# BESt-module_v_1_3.net
KiCad netlist of a schematic drawn in EAGLE
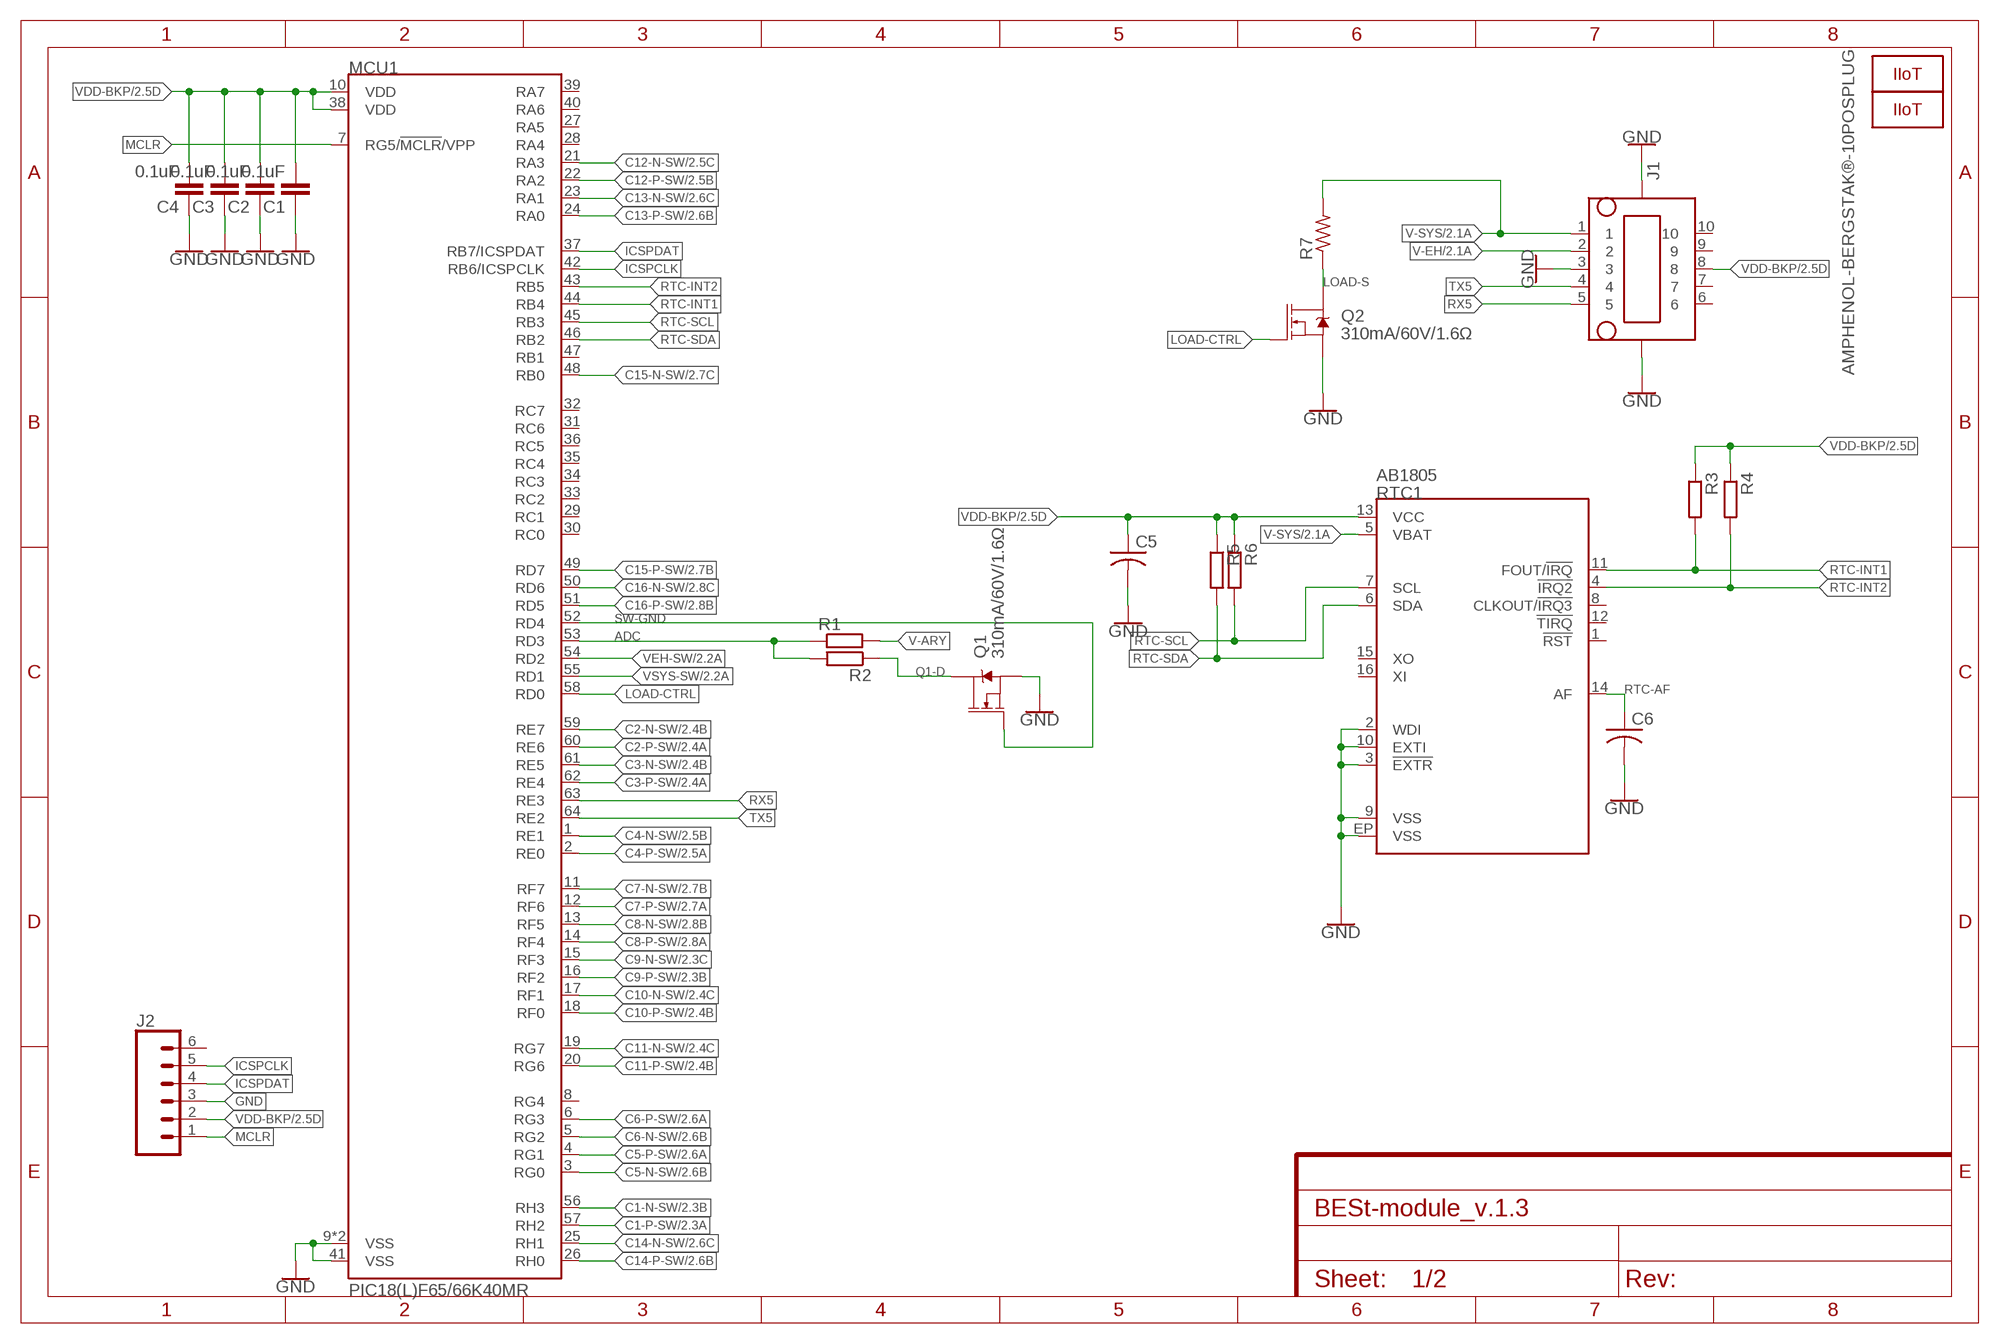
[diagram p0: schematic, sheet 1]
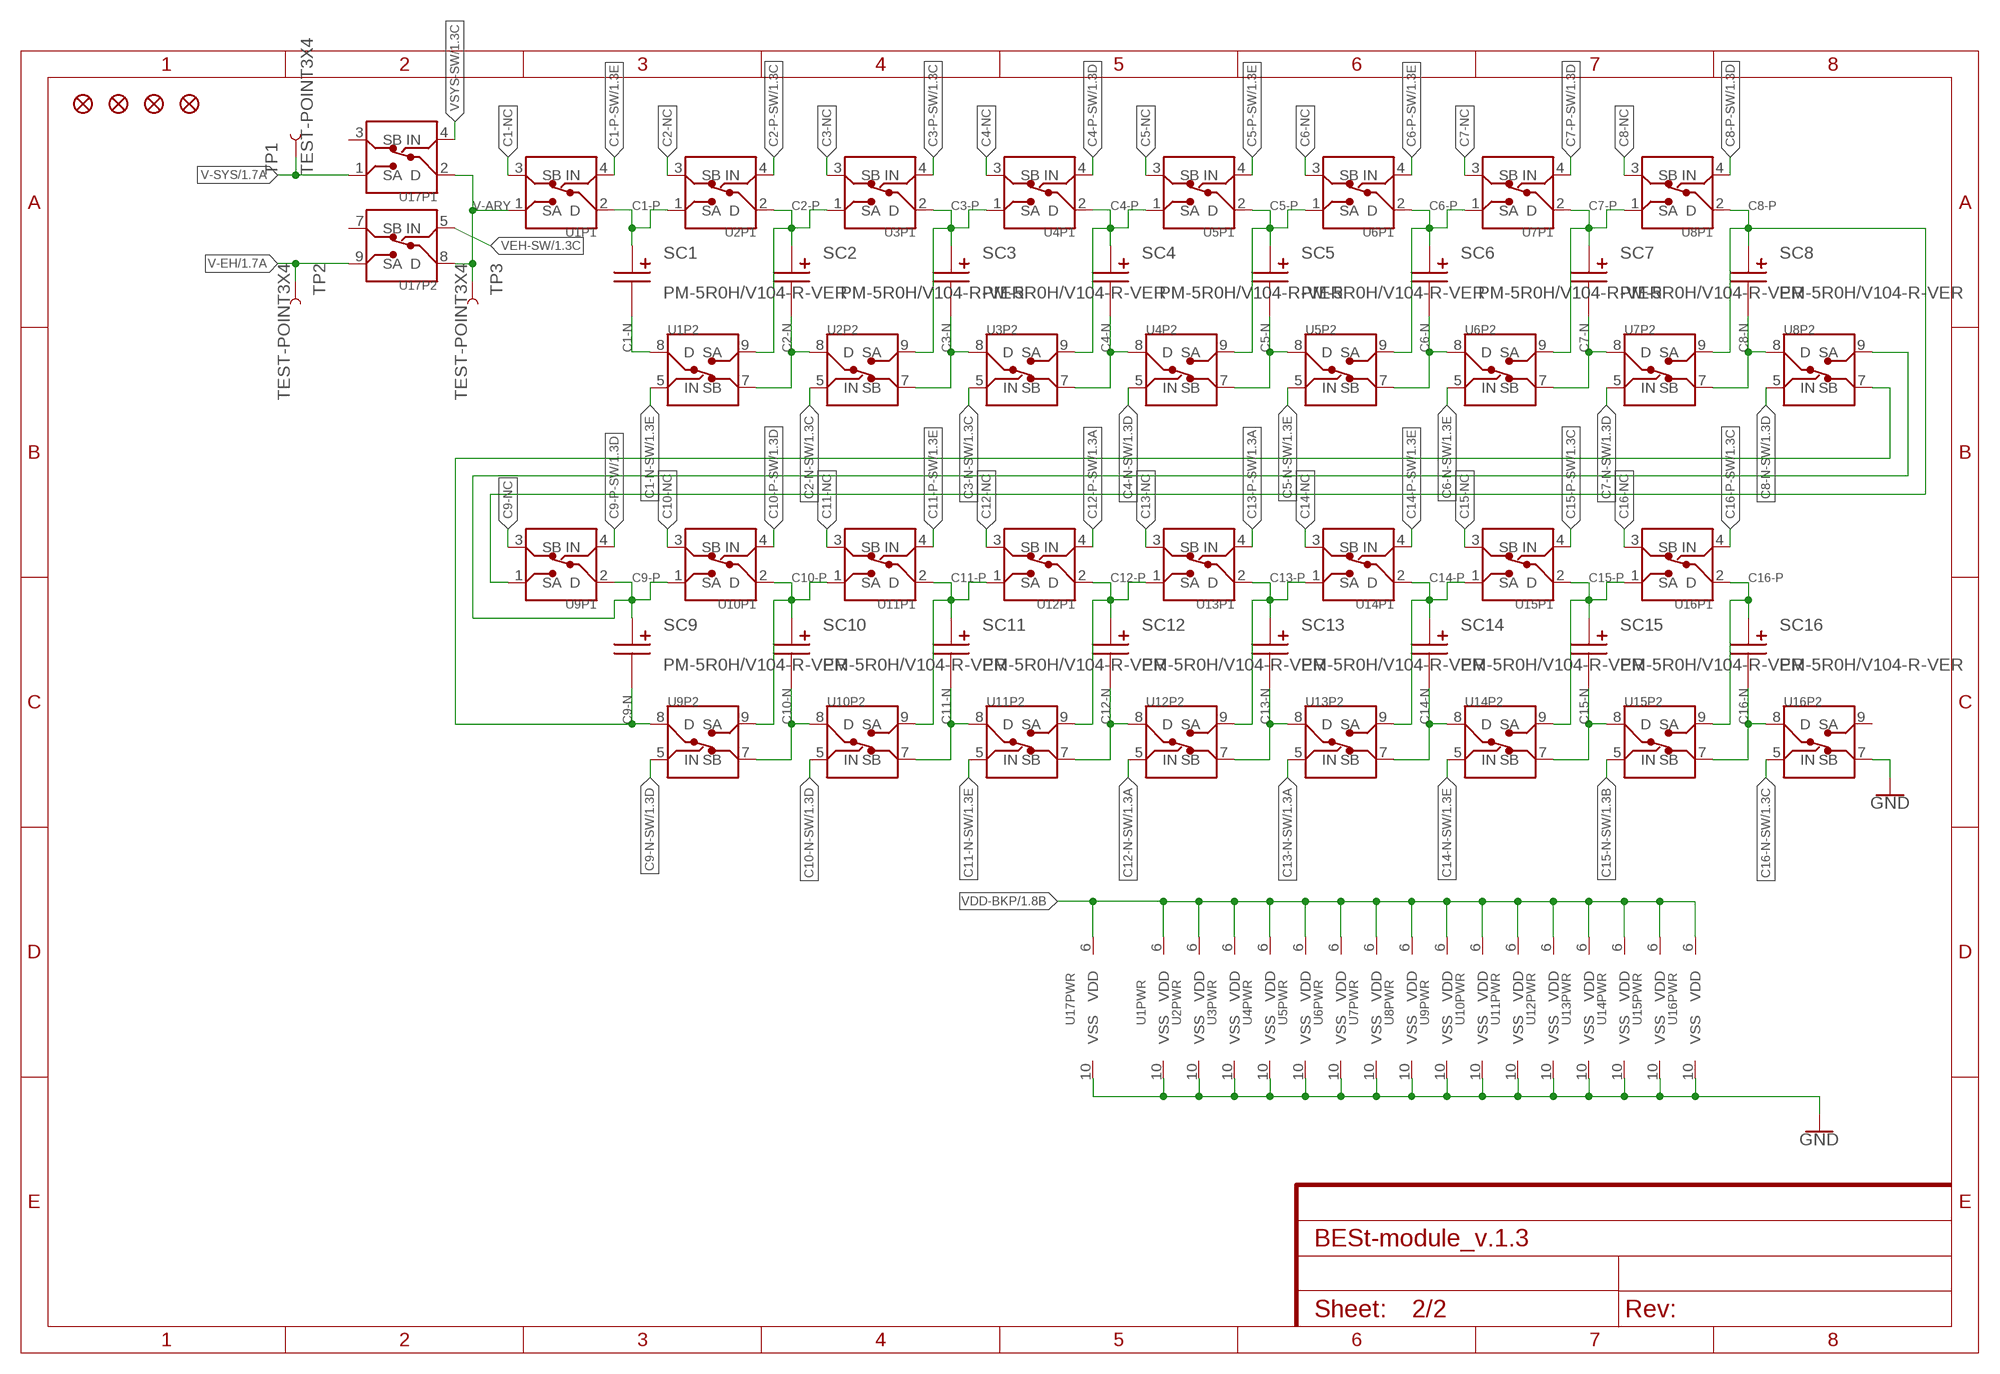
[diagram p1: schematic, sheet 2]

(export (version "E")
  (design (tool "Eeschema 10.0.6"))
  (components
    (comp (ref "FD1")
      (value "FIDUCIAL1X2")
      (footprint "eagle-import:FIDUCIAL-1X2")
      (libsource (lib "eagle-import") (part "FIDUCIAL1X2"))
    )
    (comp (ref "FD2")
      (value "FIDUCIAL1X2")
      (footprint "eagle-import:FIDUCIAL-1X2")
      (libsource (lib "eagle-import") (part "FIDUCIAL1X2"))
    )
    (comp (ref "FD3")
      (value "FIDUCIAL1X2")
      (footprint "eagle-import:FIDUCIAL-1X2")
      (libsource (lib "eagle-import") (part "FIDUCIAL1X2"))
    )
    (comp (ref "FD4")
      (value "FIDUCIAL1X2")
      (footprint "eagle-import:FIDUCIAL-1X2")
      (libsource (lib "eagle-import") (part "FIDUCIAL1X2"))
    )
    (comp (ref "SC1")
      (value "PM-5R0H/V104-R-VER")
      (footprint "eagle-import:EATON-13X11.3X6-V")
      (libsource (lib "eagle-import") (part "PM-5R0H/V104-R-VER"))
    )
    (comp (ref "SC2")
      (value "PM-5R0H/V104-R-VER")
      (footprint "eagle-import:EATON-13X11.3X6-V")
      (libsource (lib "eagle-import") (part "PM-5R0H/V104-R-VER"))
    )
    (comp (ref "SC3")
      (value "PM-5R0H/V104-R-VER")
      (footprint "eagle-import:EATON-13X11.3X6-V")
      (libsource (lib "eagle-import") (part "PM-5R0H/V104-R-VER"))
    )
    (comp (ref "SC4")
      (value "PM-5R0H/V104-R-VER")
      (footprint "eagle-import:EATON-13X11.3X6-V")
      (libsource (lib "eagle-import") (part "PM-5R0H/V104-R-VER"))
    )
    (comp (ref "SC5")
      (value "PM-5R0H/V104-R-VER")
      (footprint "eagle-import:EATON-13X11.3X6-V")
      (libsource (lib "eagle-import") (part "PM-5R0H/V104-R-VER"))
    )
    (comp (ref "SC6")
      (value "PM-5R0H/V104-R-VER")
      (footprint "eagle-import:EATON-13X11.3X6-V")
      (libsource (lib "eagle-import") (part "PM-5R0H/V104-R-VER"))
    )
    (comp (ref "SC7")
      (value "PM-5R0H/V104-R-VER")
      (footprint "eagle-import:EATON-13X11.3X6-V")
      (libsource (lib "eagle-import") (part "PM-5R0H/V104-R-VER"))
    )
    (comp (ref "SC8")
      (value "PM-5R0H/V104-R-VER")
      (footprint "eagle-import:EATON-13X11.3X6-V")
      (libsource (lib "eagle-import") (part "PM-5R0H/V104-R-VER"))
    )
    (comp (ref "SC9")
      (value "PM-5R0H/V104-R-VER")
      (footprint "eagle-import:EATON-13X11.3X6-V")
      (libsource (lib "eagle-import") (part "PM-5R0H/V104-R-VER"))
    )
    (comp (ref "SC10")
      (value "PM-5R0H/V104-R-VER")
      (footprint "eagle-import:EATON-13X11.3X6-V")
      (libsource (lib "eagle-import") (part "PM-5R0H/V104-R-VER"))
    )
    (comp (ref "SC11")
      (value "PM-5R0H/V104-R-VER")
      (footprint "eagle-import:EATON-13X11.3X6-V")
      (libsource (lib "eagle-import") (part "PM-5R0H/V104-R-VER"))
    )
    (comp (ref "SC12")
      (value "PM-5R0H/V104-R-VER")
      (footprint "eagle-import:EATON-13X11.3X6-V")
      (libsource (lib "eagle-import") (part "PM-5R0H/V104-R-VER"))
    )
    (comp (ref "SC13")
      (value "PM-5R0H/V104-R-VER")
      (footprint "eagle-import:EATON-13X11.3X6-V")
      (libsource (lib "eagle-import") (part "PM-5R0H/V104-R-VER"))
    )
    (comp (ref "SC14")
      (value "PM-5R0H/V104-R-VER")
      (footprint "eagle-import:EATON-13X11.3X6-V")
      (libsource (lib "eagle-import") (part "PM-5R0H/V104-R-VER"))
    )
    (comp (ref "SC15")
      (value "PM-5R0H/V104-R-VER")
      (footprint "eagle-import:EATON-13X11.3X6-V")
      (libsource (lib "eagle-import") (part "PM-5R0H/V104-R-VER"))
    )
    (comp (ref "SC16")
      (value "PM-5R0H/V104-R-VER")
      (footprint "eagle-import:EATON-13X11.3X6-V")
      (libsource (lib "eagle-import") (part "PM-5R0H/V104-R-VER"))
    )
    (comp (ref "TP1")
      (value "TEST-POINT3X4")
      (footprint "eagle-import:PAD.03X.04")
      (libsource (lib "eagle-import") (part "TEST-POINT3X4"))
    )
    (comp (ref "TP2")
      (value "TEST-POINT3X4")
      (footprint "eagle-import:PAD.03X.04")
      (libsource (lib "eagle-import") (part "TEST-POINT3X4"))
    )
    (comp (ref "TP3")
      (value "TEST-POINT3X4")
      (footprint "eagle-import:PAD.03X.04")
      (libsource (lib "eagle-import") (part "TEST-POINT3X4"))
    )
    (comp (ref "U1")
      (value "ADG824")
      (footprint "eagle-import:CP-10-10")
      (libsource (lib "eagle-import") (part "ADG824"))
    )
    (comp (ref "U2")
      (value "ADG824")
      (footprint "eagle-import:CP-10-10")
      (libsource (lib "eagle-import") (part "ADG824"))
    )
    (comp (ref "U3")
      (value "ADG824")
      (footprint "eagle-import:CP-10-10")
      (libsource (lib "eagle-import") (part "ADG824"))
    )
    (comp (ref "U4")
      (value "ADG824")
      (footprint "eagle-import:CP-10-10")
      (libsource (lib "eagle-import") (part "ADG824"))
    )
    (comp (ref "U5")
      (value "ADG824")
      (footprint "eagle-import:CP-10-10")
      (libsource (lib "eagle-import") (part "ADG824"))
    )
    (comp (ref "U6")
      (value "ADG824")
      (footprint "eagle-import:CP-10-10")
      (libsource (lib "eagle-import") (part "ADG824"))
    )
    (comp (ref "U7")
      (value "ADG824")
      (footprint "eagle-import:CP-10-10")
      (libsource (lib "eagle-import") (part "ADG824"))
    )
    (comp (ref "U8")
      (value "ADG824")
      (footprint "eagle-import:CP-10-10")
      (libsource (lib "eagle-import") (part "ADG824"))
    )
    (comp (ref "U9")
      (value "ADG824")
      (footprint "eagle-import:CP-10-10")
      (libsource (lib "eagle-import") (part "ADG824"))
    )
    (comp (ref "U10")
      (value "ADG824")
      (footprint "eagle-import:CP-10-10")
      (libsource (lib "eagle-import") (part "ADG824"))
    )
    (comp (ref "U11")
      (value "ADG824")
      (footprint "eagle-import:CP-10-10")
      (libsource (lib "eagle-import") (part "ADG824"))
    )
    (comp (ref "U12")
      (value "ADG824")
      (footprint "eagle-import:CP-10-10")
      (libsource (lib "eagle-import") (part "ADG824"))
    )
    (comp (ref "U13")
      (value "ADG824")
      (footprint "eagle-import:CP-10-10")
      (libsource (lib "eagle-import") (part "ADG824"))
    )
    (comp (ref "U14")
      (value "ADG824")
      (footprint "eagle-import:CP-10-10")
      (libsource (lib "eagle-import") (part "ADG824"))
    )
    (comp (ref "U15")
      (value "ADG824")
      (footprint "eagle-import:CP-10-10")
      (libsource (lib "eagle-import") (part "ADG824"))
    )
    (comp (ref "U16")
      (value "ADG824")
      (footprint "eagle-import:CP-10-10")
      (libsource (lib "eagle-import") (part "ADG824"))
    )
    (comp (ref "U17")
      (value "ADG824")
      (footprint "eagle-import:CP-10-10")
      (libsource (lib "eagle-import") (part "ADG824"))
    )
    (comp (ref "C1")
      (value "0.1uF")
      (footprint "eagle-import:0603")
      (libsource (lib "eagle-import") (part "0.1UF-0603-25V-5%"))
    )
    (comp (ref "C2")
      (value "0.1uF")
      (footprint "eagle-import:0603")
      (libsource (lib "eagle-import") (part "0.1UF-0603-25V-5%"))
    )
    (comp (ref "C3")
      (value "0.1uF")
      (footprint "eagle-import:0603")
      (libsource (lib "eagle-import") (part "0.1UF-0603-25V-5%"))
    )
    (comp (ref "C4")
      (value "0.1uF")
      (footprint "eagle-import:0603")
      (libsource (lib "eagle-import") (part "0.1UF-0603-25V-5%"))
    )
    (comp (ref "C5")
      (value "C-USC0402")
      (footprint "eagle-import:C0402")
      (libsource (lib "eagle-import") (part "C-USC0402"))
    )
    (comp (ref "C6")
      (value "C-USC0402")
      (footprint "eagle-import:C0402")
      (libsource (lib "eagle-import") (part "C-USC0402"))
    )
    (comp (ref "J1")
      (value "AMPHENOL-BERGSTAK®-10POSPLUG")
      (footprint "eagle-import:10132797-10POS-PLUG")
      (libsource (lib "eagle-import") (part "AMPHENOL-BERGSTAK®-10POSPLUG"))
    )
    (comp (ref "J2")
      (value "CONN_06NO_SILK_NO_POP")
      (footprint "eagle-import:1X06_NO_SILK")
      (libsource (lib "eagle-import") (part "CONN_06NO_SILK_NO_POP"))
    )
    (comp (ref "LOGO1")
      (value "IIOT")
      (footprint "eagle-import:IIOT")
      (libsource (lib "eagle-import") (part "IIOT"))
    )
    (comp (ref "LOGO2")
      (value "IIOT")
      (footprint "eagle-import:IIOT")
      (libsource (lib "eagle-import") (part "IIOT"))
    )
    (comp (ref "MCU1")
      (value "PIC18(L)F65/66K40MR")
      (footprint "eagle-import:QFN50P900X900X100-65T715N")
      (libsource (lib "eagle-import") (part "PIC18(L)F65/66K40MR"))
    )
    (comp (ref "Q1")
      (value "310mA/60V/1.6Ω")
      (footprint "eagle-import:SOT323")
      (libsource (lib "eagle-import") (part "MOSFET-NCH-2N7002PW"))
    )
    (comp (ref "Q2")
      (value "310mA/60V/1.6Ω")
      (footprint "eagle-import:SOT323")
      (libsource (lib "eagle-import") (part "MOSFET-NCH-2N7002PW"))
    )
    (comp (ref "R1")
      (value "R-EU_R0402")
      (footprint "eagle-import:R0402")
      (libsource (lib "eagle-import") (part "R-EU_R0402"))
    )
    (comp (ref "R2")
      (value "R-EU_R0402")
      (footprint "eagle-import:R0402")
      (libsource (lib "eagle-import") (part "R-EU_R0402"))
    )
    (comp (ref "R3")
      (value "R-EU_R0402")
      (footprint "eagle-import:R0402")
      (libsource (lib "eagle-import") (part "R-EU_R0402"))
    )
    (comp (ref "R4")
      (value "R-EU_R0402")
      (footprint "eagle-import:R0402")
      (libsource (lib "eagle-import") (part "R-EU_R0402"))
    )
    (comp (ref "R5")
      (value "R-EU_R0402")
      (footprint "eagle-import:R0402")
      (libsource (lib "eagle-import") (part "R-EU_R0402"))
    )
    (comp (ref "R6")
      (value "R-EU_R0402")
      (footprint "eagle-import:R0402")
      (libsource (lib "eagle-import") (part "R-EU_R0402"))
    )
    (comp (ref "R7")
      (value "R-US_R0805")
      (footprint "eagle-import:R0805")
      (libsource (lib "eagle-import") (part "R-US_R0805"))
    )
    (comp (ref "RTC1")
      (value "AB1805")
      (footprint "eagle-import:QFN-16-3X3")
      (libsource (lib "eagle-import") (part "AB1805"))
    )
  )
  (nets
    (net (code "1") (name "ADC") (class "Default")
      (node (ref "MCU1") (pin "53") (pinfunction "RD3_53") (pintype "bidirectional"))
      (node (ref "R1") (pin "1") (pinfunction "1_1") (pintype "passive"))
      (node (ref "R2") (pin "2") (pinfunction "2_2") (pintype "passive"))
    )
    (net (code "2") (name "C1-N") (class "Default")
      (node (ref "SC1") (pin "N") (pinfunction "N_N") (pintype "bidirectional"))
      (node (ref "U1") (pin "8") (pinfunction "D_8") (pintype "bidirectional"))
    )
    (net (code "3") (name "C1-N-SW") (class "Default")
      (node (ref "MCU1") (pin "56") (pinfunction "RH3_56") (pintype "bidirectional"))
      (node (ref "U1") (pin "5") (pinfunction "IN_5") (pintype "bidirectional"))
    )
    (net (code "4") (name "C1-NC") (class "Default")
      (node (ref "U1") (pin "3") (pinfunction "SB_3") (pintype "bidirectional"))
    )
    (net (code "5") (name "C1-P") (class "Default")
      (node (ref "SC1") (pin "P") (pinfunction "P_P") (pintype "bidirectional"))
      (node (ref "U1") (pin "2") (pinfunction "D_2") (pintype "bidirectional"))
      (node (ref "U2") (pin "1") (pinfunction "SA_1") (pintype "bidirectional"))
    )
    (net (code "6") (name "C1-P-SW") (class "Default")
      (node (ref "MCU1") (pin "57") (pinfunction "RH2_57") (pintype "bidirectional"))
      (node (ref "U1") (pin "4") (pinfunction "IN_4") (pintype "bidirectional"))
    )
    (net (code "7") (name "C2-N") (class "Default")
      (node (ref "SC2") (pin "N") (pinfunction "N_N") (pintype "bidirectional"))
      (node (ref "U1") (pin "7") (pinfunction "SB_7") (pintype "bidirectional"))
      (node (ref "U2") (pin "8") (pinfunction "D_8") (pintype "bidirectional"))
    )
    (net (code "8") (name "C2-N-SW") (class "Default")
      (node (ref "MCU1") (pin "59") (pinfunction "RE7_59") (pintype "bidirectional"))
      (node (ref "U2") (pin "5") (pinfunction "IN_5") (pintype "bidirectional"))
    )
    (net (code "9") (name "C2-NC") (class "Default")
      (node (ref "U2") (pin "3") (pinfunction "SB_3") (pintype "bidirectional"))
    )
    (net (code "10") (name "C2-P") (class "Default")
      (node (ref "SC2") (pin "P") (pinfunction "P_P") (pintype "bidirectional"))
      (node (ref "U1") (pin "9") (pinfunction "SA_9") (pintype "bidirectional"))
      (node (ref "U2") (pin "2") (pinfunction "D_2") (pintype "bidirectional"))
      (node (ref "U3") (pin "1") (pinfunction "SA_1") (pintype "bidirectional"))
    )
    (net (code "11") (name "C2-P-SW") (class "Default")
      (node (ref "MCU1") (pin "60") (pinfunction "RE6_60") (pintype "bidirectional"))
      (node (ref "U2") (pin "4") (pinfunction "IN_4") (pintype "bidirectional"))
    )
    (net (code "12") (name "C3-N") (class "Default")
      (node (ref "SC3") (pin "N") (pinfunction "N_N") (pintype "bidirectional"))
      (node (ref "U2") (pin "7") (pinfunction "SB_7") (pintype "bidirectional"))
      (node (ref "U3") (pin "8") (pinfunction "D_8") (pintype "bidirectional"))
    )
    (net (code "13") (name "C3-N-SW") (class "Default")
      (node (ref "MCU1") (pin "61") (pinfunction "RE5_61") (pintype "bidirectional"))
      (node (ref "U3") (pin "5") (pinfunction "IN_5") (pintype "bidirectional"))
    )
    (net (code "14") (name "C3-NC") (class "Default")
      (node (ref "U3") (pin "3") (pinfunction "SB_3") (pintype "bidirectional"))
    )
    (net (code "15") (name "C3-P") (class "Default")
      (node (ref "SC3") (pin "P") (pinfunction "P_P") (pintype "bidirectional"))
      (node (ref "U2") (pin "9") (pinfunction "SA_9") (pintype "bidirectional"))
      (node (ref "U3") (pin "2") (pinfunction "D_2") (pintype "bidirectional"))
      (node (ref "U4") (pin "1") (pinfunction "SA_1") (pintype "bidirectional"))
    )
    (net (code "16") (name "C3-P-SW") (class "Default")
      (node (ref "MCU1") (pin "62") (pinfunction "RE4_62") (pintype "bidirectional"))
      (node (ref "U3") (pin "4") (pinfunction "IN_4") (pintype "bidirectional"))
    )
    (net (code "17") (name "C4-N") (class "Default")
      (node (ref "SC4") (pin "N") (pinfunction "N_N") (pintype "bidirectional"))
      (node (ref "U3") (pin "7") (pinfunction "SB_7") (pintype "bidirectional"))
      (node (ref "U4") (pin "8") (pinfunction "D_8") (pintype "bidirectional"))
    )
    (net (code "18") (name "C4-N-SW") (class "Default")
      (node (ref "MCU1") (pin "1") (pinfunction "RE1_1") (pintype "bidirectional"))
      (node (ref "U4") (pin "5") (pinfunction "IN_5") (pintype "bidirectional"))
    )
    (net (code "19") (name "C4-NC") (class "Default")
      (node (ref "U4") (pin "3") (pinfunction "SB_3") (pintype "bidirectional"))
    )
    (net (code "20") (name "C4-P") (class "Default")
      (node (ref "SC4") (pin "P") (pinfunction "P_P") (pintype "bidirectional"))
      (node (ref "U3") (pin "9") (pinfunction "SA_9") (pintype "bidirectional"))
      (node (ref "U4") (pin "2") (pinfunction "D_2") (pintype "bidirectional"))
      (node (ref "U5") (pin "1") (pinfunction "SA_1") (pintype "bidirectional"))
    )
    (net (code "21") (name "C4-P-SW") (class "Default")
      (node (ref "MCU1") (pin "2") (pinfunction "RE0_2") (pintype "bidirectional"))
      (node (ref "U4") (pin "4") (pinfunction "IN_4") (pintype "bidirectional"))
    )
    (net (code "22") (name "C5-N") (class "Default")
      (node (ref "SC5") (pin "N") (pinfunction "N_N") (pintype "bidirectional"))
      (node (ref "U4") (pin "7") (pinfunction "SB_7") (pintype "bidirectional"))
      (node (ref "U5") (pin "8") (pinfunction "D_8") (pintype "bidirectional"))
    )
    (net (code "23") (name "C5-N-SW") (class "Default")
      (node (ref "MCU1") (pin "3") (pinfunction "RG0_3") (pintype "bidirectional"))
      (node (ref "U5") (pin "5") (pinfunction "IN_5") (pintype "bidirectional"))
    )
    (net (code "24") (name "C5-NC") (class "Default")
      (node (ref "U5") (pin "3") (pinfunction "SB_3") (pintype "bidirectional"))
    )
    (net (code "25") (name "C5-P") (class "Default")
      (node (ref "SC5") (pin "P") (pinfunction "P_P") (pintype "bidirectional"))
      (node (ref "U4") (pin "9") (pinfunction "SA_9") (pintype "bidirectional"))
      (node (ref "U5") (pin "2") (pinfunction "D_2") (pintype "bidirectional"))
      (node (ref "U6") (pin "1") (pinfunction "SA_1") (pintype "bidirectional"))
    )
    (net (code "26") (name "C5-P-SW") (class "Default")
      (node (ref "MCU1") (pin "4") (pinfunction "RG1_4") (pintype "bidirectional"))
      (node (ref "U5") (pin "4") (pinfunction "IN_4") (pintype "bidirectional"))
    )
    (net (code "27") (name "C6-N") (class "Default")
      (node (ref "SC6") (pin "N") (pinfunction "N_N") (pintype "bidirectional"))
      (node (ref "U5") (pin "7") (pinfunction "SB_7") (pintype "bidirectional"))
      (node (ref "U6") (pin "8") (pinfunction "D_8") (pintype "bidirectional"))
    )
    (net (code "28") (name "C6-N-SW") (class "Default")
      (node (ref "MCU1") (pin "5") (pinfunction "RG2_5") (pintype "bidirectional"))
      (node (ref "U6") (pin "5") (pinfunction "IN_5") (pintype "bidirectional"))
    )
    (net (code "29") (name "C6-NC") (class "Default")
      (node (ref "U6") (pin "3") (pinfunction "SB_3") (pintype "bidirectional"))
    )
    (net (code "30") (name "C6-P") (class "Default")
      (node (ref "SC6") (pin "P") (pinfunction "P_P") (pintype "bidirectional"))
      (node (ref "U5") (pin "9") (pinfunction "SA_9") (pintype "bidirectional"))
      (node (ref "U6") (pin "2") (pinfunction "D_2") (pintype "bidirectional"))
      (node (ref "U7") (pin "1") (pinfunction "SA_1") (pintype "bidirectional"))
    )
    (net (code "31") (name "C6-P-SW") (class "Default")
      (node (ref "MCU1") (pin "6") (pinfunction "RG3_6") (pintype "bidirectional"))
      (node (ref "U6") (pin "4") (pinfunction "IN_4") (pintype "bidirectional"))
    )
    (net (code "32") (name "C7-N") (class "Default")
      (node (ref "SC7") (pin "N") (pinfunction "N_N") (pintype "bidirectional"))
      (node (ref "U6") (pin "7") (pinfunction "SB_7") (pintype "bidirectional"))
      (node (ref "U7") (pin "8") (pinfunction "D_8") (pintype "bidirectional"))
    )
    (net (code "33") (name "C7-N-SW") (class "Default")
      (node (ref "MCU1") (pin "11") (pinfunction "RF7_11") (pintype "bidirectional"))
      (node (ref "U7") (pin "5") (pinfunction "IN_5") (pintype "bidirectional"))
    )
    (net (code "34") (name "C7-NC") (class "Default")
      (node (ref "U7") (pin "3") (pinfunction "SB_3") (pintype "bidirectional"))
    )
    (net (code "35") (name "C7-P") (class "Default")
      (node (ref "SC7") (pin "P") (pinfunction "P_P") (pintype "bidirectional"))
      (node (ref "U6") (pin "9") (pinfunction "SA_9") (pintype "bidirectional"))
      (node (ref "U7") (pin "2") (pinfunction "D_2") (pintype "bidirectional"))
      (node (ref "U8") (pin "1") (pinfunction "SA_1") (pintype "bidirectional"))
    )
    (net (code "36") (name "C7-P-SW") (class "Default")
      (node (ref "MCU1") (pin "12") (pinfunction "RF6_12") (pintype "bidirectional"))
      (node (ref "U7") (pin "4") (pinfunction "IN_4") (pintype "bidirectional"))
    )
    (net (code "37") (name "C8-N") (class "Default")
      (node (ref "SC8") (pin "N") (pinfunction "N_N") (pintype "bidirectional"))
      (node (ref "U7") (pin "7") (pinfunction "SB_7") (pintype "bidirectional"))
      (node (ref "U8") (pin "8") (pinfunction "D_8") (pintype "bidirectional"))
    )
    (net (code "38") (name "C8-N-SW") (class "Default")
      (node (ref "MCU1") (pin "13") (pinfunction "RF5_13") (pintype "bidirectional"))
      (node (ref "U8") (pin "5") (pinfunction "IN_5") (pintype "bidirectional"))
    )
    (net (code "39") (name "C8-NC") (class "Default")
      (node (ref "U8") (pin "3") (pinfunction "SB_3") (pintype "bidirectional"))
    )
    (net (code "40") (name "C8-P") (class "Default")
      (node (ref "SC8") (pin "P") (pinfunction "P_P") (pintype "bidirectional"))
      (node (ref "U7") (pin "9") (pinfunction "SA_9") (pintype "bidirectional"))
      (node (ref "U8") (pin "2") (pinfunction "D_2") (pintype "bidirectional"))
      (node (ref "U9") (pin "1") (pinfunction "SA_1") (pintype "bidirectional"))
    )
    (net (code "41") (name "C8-P-SW") (class "Default")
      (node (ref "MCU1") (pin "14") (pinfunction "RF4_14") (pintype "bidirectional"))
      (node (ref "U8") (pin "4") (pinfunction "IN_4") (pintype "bidirectional"))
    )
    (net (code "42") (name "C9-N") (class "Default")
      (node (ref "SC9") (pin "N") (pinfunction "N_N") (pintype "bidirectional"))
      (node (ref "U8") (pin "7") (pinfunction "SB_7") (pintype "bidirectional"))
      (node (ref "U9") (pin "8") (pinfunction "D_8") (pintype "bidirectional"))
    )
    (net (code "43") (name "C9-N-SW") (class "Default")
      (node (ref "MCU1") (pin "15") (pinfunction "RF3_15") (pintype "bidirectional"))
      (node (ref "U9") (pin "5") (pinfunction "IN_5") (pintype "bidirectional"))
    )
    (net (code "44") (name "C9-NC") (class "Default")
      (node (ref "U9") (pin "3") (pinfunction "SB_3") (pintype "bidirectional"))
    )
    (net (code "45") (name "C9-P") (class "Default")
      (node (ref "SC9") (pin "P") (pinfunction "P_P") (pintype "bidirectional"))
      (node (ref "U10") (pin "1") (pinfunction "SA_1") (pintype "bidirectional"))
      (node (ref "U8") (pin "9") (pinfunction "SA_9") (pintype "bidirectional"))
      (node (ref "U9") (pin "2") (pinfunction "D_2") (pintype "bidirectional"))
    )
    (net (code "46") (name "C9-P-SW") (class "Default")
      (node (ref "MCU1") (pin "16") (pinfunction "RF2_16") (pintype "bidirectional"))
      (node (ref "U9") (pin "4") (pinfunction "IN_4") (pintype "bidirectional"))
    )
    (net (code "47") (name "C10-N") (class "Default")
      (node (ref "SC10") (pin "N") (pinfunction "N_N") (pintype "bidirectional"))
      (node (ref "U10") (pin "8") (pinfunction "D_8") (pintype "bidirectional"))
      (node (ref "U9") (pin "7") (pinfunction "SB_7") (pintype "bidirectional"))
    )
    (net (code "48") (name "C10-N-SW") (class "Default")
      (node (ref "MCU1") (pin "17") (pinfunction "RF1_17") (pintype "bidirectional"))
      (node (ref "U10") (pin "5") (pinfunction "IN_5") (pintype "bidirectional"))
    )
    (net (code "49") (name "C10-NC") (class "Default")
      (node (ref "U10") (pin "3") (pinfunction "SB_3") (pintype "bidirectional"))
    )
    (net (code "50") (name "C10-P") (class "Default")
      (node (ref "SC10") (pin "P") (pinfunction "P_P") (pintype "bidirectional"))
      (node (ref "U10") (pin "2") (pinfunction "D_2") (pintype "bidirectional"))
      (node (ref "U11") (pin "1") (pinfunction "SA_1") (pintype "bidirectional"))
      (node (ref "U9") (pin "9") (pinfunction "SA_9") (pintype "bidirectional"))
    )
    (net (code "51") (name "C10-P-SW") (class "Default")
      (node (ref "MCU1") (pin "18") (pinfunction "RF0_18") (pintype "bidirectional"))
      (node (ref "U10") (pin "4") (pinfunction "IN_4") (pintype "bidirectional"))
    )
    (net (code "52") (name "C11-N") (class "Default")
      (node (ref "SC11") (pin "N") (pinfunction "N_N") (pintype "bidirectional"))
      (node (ref "U10") (pin "7") (pinfunction "SB_7") (pintype "bidirectional"))
      (node (ref "U11") (pin "8") (pinfunction "D_8") (pintype "bidirectional"))
    )
    (net (code "53") (name "C11-N-SW") (class "Default")
      (node (ref "MCU1") (pin "19") (pinfunction "RG7_19") (pintype "bidirectional"))
      (node (ref "U11") (pin "5") (pinfunction "IN_5") (pintype "bidirectional"))
    )
    (net (code "54") (name "C11-NC") (class "Default")
      (node (ref "U11") (pin "3") (pinfunction "SB_3") (pintype "bidirectional"))
    )
    (net (code "55") (name "C11-P") (class "Default")
      (node (ref "SC11") (pin "P") (pinfunction "P_P") (pintype "bidirectional"))
      (node (ref "U10") (pin "9") (pinfunction "SA_9") (pintype "bidirectional"))
      (node (ref "U11") (pin "2") (pinfunction "D_2") (pintype "bidirectional"))
      (node (ref "U12") (pin "1") (pinfunction "SA_1") (pintype "bidirectional"))
    )
    (net (code "56") (name "C11-P-SW") (class "Default")
      (node (ref "MCU1") (pin "20") (pinfunction "RG6_20") (pintype "bidirectional"))
      (node (ref "U11") (pin "4") (pinfunction "IN_4") (pintype "bidirectional"))
    )
    (net (code "57") (name "C12-N") (class "Default")
      (node (ref "SC12") (pin "N") (pinfunction "N_N") (pintype "bidirectional"))
      (node (ref "U11") (pin "7") (pinfunction "SB_7") (pintype "bidirectional"))
      (node (ref "U12") (pin "8") (pinfunction "D_8") (pintype "bidirectional"))
    )
    (net (code "58") (name "C12-N-SW") (class "Default")
      (node (ref "MCU1") (pin "21") (pinfunction "RA3_21") (pintype "bidirectional"))
      (node (ref "U12") (pin "5") (pinfunction "IN_5") (pintype "bidirectional"))
    )
    (net (code "59") (name "C12-NC") (class "Default")
      (node (ref "U12") (pin "3") (pinfunction "SB_3") (pintype "bidirectional"))
    )
    (net (code "60") (name "C12-P") (class "Default")
      (node (ref "SC12") (pin "P") (pinfunction "P_P") (pintype "bidirectional"))
      (node (ref "U11") (pin "9") (pinfunction "SA_9") (pintype "bidirectional"))
      (node (ref "U12") (pin "2") (pinfunction "D_2") (pintype "bidirectional"))
      (node (ref "U13") (pin "1") (pinfunction "SA_1") (pintype "bidirectional"))
    )
    (net (code "61") (name "C12-P-SW") (class "Default")
      (node (ref "MCU1") (pin "22") (pinfunction "RA2_22") (pintype "bidirectional"))
      (node (ref "U12") (pin "4") (pinfunction "IN_4") (pintype "bidirectional"))
    )
    (net (code "62") (name "C13-N") (class "Default")
      (node (ref "SC13") (pin "N") (pinfunction "N_N") (pintype "bidirectional"))
      (node (ref "U12") (pin "7") (pinfunction "SB_7") (pintype "bidirectional"))
      (node (ref "U13") (pin "8") (pinfunction "D_8") (pintype "bidirectional"))
    )
    (net (code "63") (name "C13-N-SW") (class "Default")
      (node (ref "MCU1") (pin "23") (pinfunction "RA1_23") (pintype "bidirectional"))
      (node (ref "U13") (pin "5") (pinfunction "IN_5") (pintype "bidirectional"))
    )
    (net (code "64") (name "C13-NC") (class "Default")
      (node (ref "U13") (pin "3") (pinfunction "SB_3") (pintype "bidirectional"))
    )
    (net (code "65") (name "C13-P") (class "Default")
      (node (ref "SC13") (pin "P") (pinfunction "P_P") (pintype "bidirectional"))
      (node (ref "U12") (pin "9") (pinfunction "SA_9") (pintype "bidirectional"))
      (node (ref "U13") (pin "2") (pinfunction "D_2") (pintype "bidirectional"))
      (node (ref "U14") (pin "1") (pinfunction "SA_1") (pintype "bidirectional"))
    )
    (net (code "66") (name "C13-P-SW") (class "Default")
      (node (ref "MCU1") (pin "24") (pinfunction "RA0_24") (pintype "bidirectional"))
      (node (ref "U13") (pin "4") (pinfunction "IN_4") (pintype "bidirectional"))
    )
    (net (code "67") (name "C14-N") (class "Default")
      (node (ref "SC14") (pin "N") (pinfunction "N_N") (pintype "bidirectional"))
      (node (ref "U13") (pin "7") (pinfunction "SB_7") (pintype "bidirectional"))
      (node (ref "U14") (pin "8") (pinfunction "D_8") (pintype "bidirectional"))
    )
    (net (code "68") (name "C14-N-SW") (class "Default")
      (node (ref "MCU1") (pin "25") (pinfunction "RH1_25") (pintype "bidirectional"))
      (node (ref "U14") (pin "5") (pinfunction "IN_5") (pintype "bidirectional"))
    )
    (net (code "69") (name "C14-NC") (class "Default")
      (node (ref "U14") (pin "3") (pinfunction "SB_3") (pintype "bidirectional"))
    )
    (net (code "70") (name "C14-P") (class "Default")
      (node (ref "SC14") (pin "P") (pinfunction "P_P") (pintype "bidirectional"))
      (node (ref "U13") (pin "9") (pinfunction "SA_9") (pintype "bidirectional"))
      (node (ref "U14") (pin "2") (pinfunction "D_2") (pintype "bidirectional"))
      (node (ref "U15") (pin "1") (pinfunction "SA_1") (pintype "bidirectional"))
    )
    (net (code "71") (name "C14-P-SW") (class "Default")
      (node (ref "MCU1") (pin "26") (pinfunction "RH0_26") (pintype "bidirectional"))
      (node (ref "U14") (pin "4") (pinfunction "IN_4") (pintype "bidirectional"))
    )
    (net (code "72") (name "C15-N") (class "Default")
      (node (ref "SC15") (pin "N") (pinfunction "N_N") (pintype "bidirectional"))
      (node (ref "U14") (pin "7") (pinfunction "SB_7") (pintype "bidirectional"))
      (node (ref "U15") (pin "8") (pinfunction "D_8") (pintype "bidirectional"))
    )
    (net (code "73") (name "C15-N-SW") (class "Default")
      (node (ref "MCU1") (pin "48") (pinfunction "RB0_48") (pintype "bidirectional"))
      (node (ref "U15") (pin "5") (pinfunction "IN_5") (pintype "bidirectional"))
    )
    (net (code "74") (name "C15-NC") (class "Default")
      (node (ref "U15") (pin "3") (pinfunction "SB_3") (pintype "bidirectional"))
    )
    (net (code "75") (name "C15-P") (class "Default")
      (node (ref "SC15") (pin "P") (pinfunction "P_P") (pintype "bidirectional"))
      (node (ref "U14") (pin "9") (pinfunction "SA_9") (pintype "bidirectional"))
      (node (ref "U15") (pin "2") (pinfunction "D_2") (pintype "bidirectional"))
      (node (ref "U16") (pin "1") (pinfunction "SA_1") (pintype "bidirectional"))
    )
    (net (code "76") (name "C15-P-SW") (class "Default")
      (node (ref "MCU1") (pin "49") (pinfunction "RD7_49") (pintype "bidirectional"))
      (node (ref "U15") (pin "4") (pinfunction "IN_4") (pintype "bidirectional"))
    )
    (net (code "77") (name "C16-N") (class "Default")
      (node (ref "SC16") (pin "N") (pinfunction "N_N") (pintype "bidirectional"))
      (node (ref "U15") (pin "7") (pinfunction "SB_7") (pintype "bidirectional"))
      (node (ref "U16") (pin "8") (pinfunction "D_8") (pintype "bidirectional"))
    )
    (net (code "78") (name "C16-N-SW") (class "Default")
      (node (ref "MCU1") (pin "50") (pinfunction "RD6_50") (pintype "bidirectional"))
      (node (ref "U16") (pin "5") (pinfunction "IN_5") (pintype "bidirectional"))
    )
    (net (code "79") (name "C16-NC") (class "Default")
      (node (ref "U16") (pin "3") (pinfunction "SB_3") (pintype "bidirectional"))
    )
    (net (code "80") (name "C16-P") (class "Default")
      (node (ref "SC16") (pin "P") (pinfunction "P_P") (pintype "bidirectional"))
      (node (ref "U15") (pin "9") (pinfunction "SA_9") (pintype "bidirectional"))
      (node (ref "U16") (pin "2") (pinfunction "D_2") (pintype "bidirectional"))
    )
    (net (code "81") (name "C16-P-SW") (class "Default")
      (node (ref "MCU1") (pin "51") (pinfunction "RD5_51") (pintype "bidirectional"))
      (node (ref "U16") (pin "4") (pinfunction "IN_4") (pintype "bidirectional"))
    )
    (net (code "82") (name "GND") (class "Default")
      (node (ref "C1") (pin "1") (pinfunction "1_1") (pintype "passive"))
      (node (ref "C2") (pin "1") (pinfunction "1_1") (pintype "passive"))
      (node (ref "C3") (pin "1") (pinfunction "1_1") (pintype "passive"))
      (node (ref "C4") (pin "1") (pinfunction "1_1") (pintype "passive"))
      (node (ref "C5") (pin "2") (pinfunction "2_2") (pintype "passive"))
      (node (ref "C6") (pin "2") (pinfunction "2_2") (pintype "passive"))
      (node (ref "J1") (pin "3") (pinfunction "3_3") (pintype "bidirectional"))
      (node (ref "J1") (pin "MNT1") (pinfunction "MNT1_MNT1") (pintype "bidirectional"))
      (node (ref "J1") (pin "MNT2") (pinfunction "MNT2_MNT2") (pintype "bidirectional"))
      (node (ref "J2") (pin "3") (pinfunction "3_3") (pintype "passive"))
      (node (ref "MCU1") (pin "41") (pinfunction "VSS_41") (pintype "bidirectional"))
      (node (ref "MCU1") (pin "65") (pinfunction "VSS_65") (pintype "bidirectional"))
      (node (ref "MCU1") (pin "9") (pinfunction "VSS_9") (pintype "bidirectional"))
      (node (ref "Q1") (pin "2") (pinfunction "S_2") (pintype "bidirectional"))
      (node (ref "Q2") (pin "2") (pinfunction "S_2") (pintype "bidirectional"))
      (node (ref "RTC1") (pin "10") (pinfunction "EXTI_10") (pintype "bidirectional"))
      (node (ref "RTC1") (pin "2") (pinfunction "WDI_2") (pintype "bidirectional"))
      (node (ref "RTC1") (pin "3") (pinfunction "~{EXTR}_3") (pintype "bidirectional"))
      (node (ref "RTC1") (pin "9") (pinfunction "VSS_9") (pintype "bidirectional"))
      (node (ref "RTC1") (pin "EP") (pinfunction "VSS_EP") (pintype "bidirectional"))
      (node (ref "U1") (pin "10") (pinfunction "VSS_10") (pintype "bidirectional"))
      (node (ref "U10") (pin "10") (pinfunction "VSS_10") (pintype "bidirectional"))
      (node (ref "U11") (pin "10") (pinfunction "VSS_10") (pintype "bidirectional"))
      (node (ref "U12") (pin "10") (pinfunction "VSS_10") (pintype "bidirectional"))
      (node (ref "U13") (pin "10") (pinfunction "VSS_10") (pintype "bidirectional"))
      (node (ref "U14") (pin "10") (pinfunction "VSS_10") (pintype "bidirectional"))
      (node (ref "U15") (pin "10") (pinfunction "VSS_10") (pintype "bidirectional"))
      (node (ref "U16") (pin "10") (pinfunction "VSS_10") (pintype "bidirectional"))
      (node (ref "U16") (pin "7") (pinfunction "SB_7") (pintype "bidirectional"))
      (node (ref "U17") (pin "10") (pinfunction "VSS_10") (pintype "bidirectional"))
      (node (ref "U2") (pin "10") (pinfunction "VSS_10") (pintype "bidirectional"))
      (node (ref "U3") (pin "10") (pinfunction "VSS_10") (pintype "bidirectional"))
      (node (ref "U4") (pin "10") (pinfunction "VSS_10") (pintype "bidirectional"))
      (node (ref "U5") (pin "10") (pinfunction "VSS_10") (pintype "bidirectional"))
      (node (ref "U6") (pin "10") (pinfunction "VSS_10") (pintype "bidirectional"))
      (node (ref "U7") (pin "10") (pinfunction "VSS_10") (pintype "bidirectional"))
      (node (ref "U8") (pin "10") (pinfunction "VSS_10") (pintype "bidirectional"))
      (node (ref "U9") (pin "10") (pinfunction "VSS_10") (pintype "bidirectional"))
    )
    (net (code "83") (name "ICSPCLK") (class "Default")
      (node (ref "J2") (pin "5") (pinfunction "5_5") (pintype "passive"))
      (node (ref "MCU1") (pin "42") (pinfunction "RB6/ICSPCLK_42") (pintype "bidirectional"))
    )
    (net (code "84") (name "ICSPDAT") (class "Default")
      (node (ref "J2") (pin "4") (pinfunction "4_4") (pintype "passive"))
      (node (ref "MCU1") (pin "37") (pinfunction "RB7/ICSPDAT_37") (pintype "bidirectional"))
    )
    (net (code "85") (name "LOAD-CTRL") (class "Default")
      (node (ref "MCU1") (pin "58") (pinfunction "RD0_58") (pintype "bidirectional"))
      (node (ref "Q2") (pin "1") (pinfunction "G_1") (pintype "bidirectional"))
    )
    (net (code "86") (name "LOAD-S") (class "Default")
      (node (ref "Q2") (pin "3") (pinfunction "D_3") (pintype "bidirectional"))
      (node (ref "R7") (pin "1") (pinfunction "1_1") (pintype "passive"))
    )
    (net (code "87") (name "MCLR") (class "Default")
      (node (ref "J2") (pin "1") (pinfunction "1_1") (pintype "passive"))
      (node (ref "MCU1") (pin "7") (pinfunction "RG5/~{MCLR}/VPP_7") (pintype "bidirectional"))
    )
    (net (code "88") (name "Q1-D") (class "Default")
      (node (ref "Q1") (pin "3") (pinfunction "D_3") (pintype "bidirectional"))
      (node (ref "R2") (pin "1") (pinfunction "1_1") (pintype "passive"))
    )
    (net (code "89") (name "RTC-AF") (class "Default")
      (node (ref "C6") (pin "1") (pinfunction "1_1") (pintype "passive"))
      (node (ref "RTC1") (pin "14") (pinfunction "AF_14") (pintype "bidirectional"))
    )
    (net (code "90") (name "RTC-INT1") (class "Default")
      (node (ref "MCU1") (pin "44") (pinfunction "RB4_44") (pintype "bidirectional"))
      (node (ref "R3") (pin "2") (pinfunction "2_2") (pintype "passive"))
      (node (ref "RTC1") (pin "11") (pinfunction "FOUT/~{IRQ}_11") (pintype "bidirectional"))
    )
    (net (code "91") (name "RTC-INT2") (class "Default")
      (node (ref "MCU1") (pin "43") (pinfunction "RB5_43") (pintype "bidirectional"))
      (node (ref "R4") (pin "2") (pinfunction "2_2") (pintype "passive"))
      (node (ref "RTC1") (pin "4") (pinfunction "~{IRQ2}_4") (pintype "bidirectional"))
    )
    (net (code "92") (name "RTC-SCL") (class "Default")
      (node (ref "MCU1") (pin "45") (pinfunction "RB3_45") (pintype "bidirectional"))
      (node (ref "R6") (pin "2") (pinfunction "2_2") (pintype "passive"))
      (node (ref "RTC1") (pin "7") (pinfunction "SCL_7") (pintype "bidirectional"))
    )
    (net (code "93") (name "RTC-SDA") (class "Default")
      (node (ref "MCU1") (pin "46") (pinfunction "RB2_46") (pintype "bidirectional"))
      (node (ref "R5") (pin "2") (pinfunction "2_2") (pintype "passive"))
      (node (ref "RTC1") (pin "6") (pinfunction "SDA_6") (pintype "bidirectional"))
    )
    (net (code "94") (name "RX5") (class "Default")
      (node (ref "J1") (pin "5") (pinfunction "5_5") (pintype "bidirectional"))
      (node (ref "MCU1") (pin "63") (pinfunction "RE3_63") (pintype "bidirectional"))
    )
    (net (code "95") (name "SW-GND") (class "Default")
      (node (ref "MCU1") (pin "52") (pinfunction "RD4_52") (pintype "bidirectional"))
      (node (ref "Q1") (pin "1") (pinfunction "G_1") (pintype "bidirectional"))
    )
    (net (code "96") (name "TX5") (class "Default")
      (node (ref "J1") (pin "4") (pinfunction "4_4") (pintype "bidirectional"))
      (node (ref "MCU1") (pin "64") (pinfunction "RE2_64") (pintype "bidirectional"))
    )
    (net (code "97") (name "V-ARY") (class "Default")
      (node (ref "R1") (pin "2") (pinfunction "2_2") (pintype "passive"))
      (node (ref "TP3") (pin "P$1") (pinfunction "1_P$1") (pintype "bidirectional"))
      (node (ref "U1") (pin "1") (pinfunction "SA_1") (pintype "bidirectional"))
      (node (ref "U17") (pin "2") (pinfunction "D_2") (pintype "bidirectional"))
      (node (ref "U17") (pin "8") (pinfunction "D_8") (pintype "bidirectional"))
    )
    (net (code "98") (name "V-EH") (class "Default")
      (node (ref "J1") (pin "2") (pinfunction "2_2") (pintype "bidirectional"))
      (node (ref "TP2") (pin "P$1") (pinfunction "1_P$1") (pintype "bidirectional"))
      (node (ref "U17") (pin "9") (pinfunction "SA_9") (pintype "bidirectional"))
    )
    (net (code "99") (name "V-SYS") (class "Default")
      (node (ref "J1") (pin "1") (pinfunction "1_1") (pintype "bidirectional"))
      (node (ref "R7") (pin "2") (pinfunction "2_2") (pintype "passive"))
      (node (ref "RTC1") (pin "5") (pinfunction "VBAT_5") (pintype "bidirectional"))
      (node (ref "TP1") (pin "P$1") (pinfunction "1_P$1") (pintype "bidirectional"))
      (node (ref "U17") (pin "1") (pinfunction "SA_1") (pintype "bidirectional"))
    )
    (net (code "100") (name "VDD-BKP") (class "Default")
      (node (ref "C1") (pin "2") (pinfunction "2_2") (pintype "passive"))
      (node (ref "C2") (pin "2") (pinfunction "2_2") (pintype "passive"))
      (node (ref "C3") (pin "2") (pinfunction "2_2") (pintype "passive"))
      (node (ref "C4") (pin "2") (pinfunction "2_2") (pintype "passive"))
      (node (ref "C5") (pin "1") (pinfunction "1_1") (pintype "passive"))
      (node (ref "J1") (pin "8") (pinfunction "8_8") (pintype "bidirectional"))
      (node (ref "J2") (pin "2") (pinfunction "2_2") (pintype "passive"))
      (node (ref "MCU1") (pin "10") (pinfunction "VDD_10") (pintype "bidirectional"))
      (node (ref "MCU1") (pin "38") (pinfunction "VDD_38") (pintype "bidirectional"))
      (node (ref "R3") (pin "1") (pinfunction "1_1") (pintype "passive"))
      (node (ref "R4") (pin "1") (pinfunction "1_1") (pintype "passive"))
      (node (ref "R5") (pin "1") (pinfunction "1_1") (pintype "passive"))
      (node (ref "R6") (pin "1") (pinfunction "1_1") (pintype "passive"))
      (node (ref "RTC1") (pin "13") (pinfunction "VCC_13") (pintype "bidirectional"))
      (node (ref "U1") (pin "6") (pinfunction "VDD_6") (pintype "bidirectional"))
      (node (ref "U10") (pin "6") (pinfunction "VDD_6") (pintype "bidirectional"))
      (node (ref "U11") (pin "6") (pinfunction "VDD_6") (pintype "bidirectional"))
      (node (ref "U12") (pin "6") (pinfunction "VDD_6") (pintype "bidirectional"))
      (node (ref "U13") (pin "6") (pinfunction "VDD_6") (pintype "bidirectional"))
      (node (ref "U14") (pin "6") (pinfunction "VDD_6") (pintype "bidirectional"))
      (node (ref "U15") (pin "6") (pinfunction "VDD_6") (pintype "bidirectional"))
      (node (ref "U16") (pin "6") (pinfunction "VDD_6") (pintype "bidirectional"))
      (node (ref "U17") (pin "6") (pinfunction "VDD_6") (pintype "bidirectional"))
      (node (ref "U2") (pin "6") (pinfunction "VDD_6") (pintype "bidirectional"))
      (node (ref "U3") (pin "6") (pinfunction "VDD_6") (pintype "bidirectional"))
      (node (ref "U4") (pin "6") (pinfunction "VDD_6") (pintype "bidirectional"))
      (node (ref "U5") (pin "6") (pinfunction "VDD_6") (pintype "bidirectional"))
      (node (ref "U6") (pin "6") (pinfunction "VDD_6") (pintype "bidirectional"))
      (node (ref "U7") (pin "6") (pinfunction "VDD_6") (pintype "bidirectional"))
      (node (ref "U8") (pin "6") (pinfunction "VDD_6") (pintype "bidirectional"))
      (node (ref "U9") (pin "6") (pinfunction "VDD_6") (pintype "bidirectional"))
    )
    (net (code "101") (name "VEH-SW") (class "Default")
      (node (ref "MCU1") (pin "54") (pinfunction "RD2_54") (pintype "bidirectional"))
      (node (ref "U17") (pin "5") (pinfunction "IN_5") (pintype "bidirectional"))
    )
    (net (code "102") (name "VSYS-SW") (class "Default")
      (node (ref "MCU1") (pin "55") (pinfunction "RD1_55") (pintype "bidirectional"))
      (node (ref "U17") (pin "4") (pinfunction "IN_4") (pintype "bidirectional"))
    )
    (net (code "103") (name "unconnected-(J1-Pad6)") (class "Default")
      (node (ref "J1") (pin "6") (pinfunction "6_6") (pintype "bidirectional"))
    )
    (net (code "104") (name "unconnected-(J1-Pad7)") (class "Default")
      (node (ref "J1") (pin "7") (pinfunction "7_7") (pintype "bidirectional"))
    )
    (net (code "105") (name "unconnected-(J1-Pad9)") (class "Default")
      (node (ref "J1") (pin "9") (pinfunction "9_9") (pintype "bidirectional"))
    )
    (net (code "106") (name "unconnected-(J1-Pad10)") (class "Default")
      (node (ref "J1") (pin "10") (pinfunction "10_10") (pintype "bidirectional"))
    )
    (net (code "107") (name "unconnected-(J2-Pad6)") (class "Default")
      (node (ref "J2") (pin "6") (pinfunction "6_6") (pintype "passive"))
    )
    (net (code "108") (name "unconnected-(MCU1-RA4-Pad28)") (class "Default")
      (node (ref "MCU1") (pin "28") (pinfunction "RA4_28") (pintype "bidirectional"))
    )
    (net (code "109") (name "unconnected-(MCU1-RA5-Pad27)") (class "Default")
      (node (ref "MCU1") (pin "27") (pinfunction "RA5_27") (pintype "bidirectional"))
    )
    (net (code "110") (name "unconnected-(MCU1-RA6-Pad40)") (class "Default")
      (node (ref "MCU1") (pin "40") (pinfunction "RA6_40") (pintype "bidirectional"))
    )
    (net (code "111") (name "unconnected-(MCU1-RA7-Pad39)") (class "Default")
      (node (ref "MCU1") (pin "39") (pinfunction "RA7_39") (pintype "bidirectional"))
    )
    (net (code "112") (name "unconnected-(MCU1-RB1-Pad47)") (class "Default")
      (node (ref "MCU1") (pin "47") (pinfunction "RB1_47") (pintype "bidirectional"))
    )
    (net (code "113") (name "unconnected-(MCU1-RC0-Pad30)") (class "Default")
      (node (ref "MCU1") (pin "30") (pinfunction "RC0_30") (pintype "bidirectional"))
    )
    (net (code "114") (name "unconnected-(MCU1-RC1-Pad29)") (class "Default")
      (node (ref "MCU1") (pin "29") (pinfunction "RC1_29") (pintype "bidirectional"))
    )
    (net (code "115") (name "unconnected-(MCU1-RC2-Pad33)") (class "Default")
      (node (ref "MCU1") (pin "33") (pinfunction "RC2_33") (pintype "bidirectional"))
    )
    (net (code "116") (name "unconnected-(MCU1-RC3-Pad34)") (class "Default")
      (node (ref "MCU1") (pin "34") (pinfunction "RC3_34") (pintype "bidirectional"))
    )
    (net (code "117") (name "unconnected-(MCU1-RC4-Pad35)") (class "Default")
      (node (ref "MCU1") (pin "35") (pinfunction "RC4_35") (pintype "bidirectional"))
    )
    (net (code "118") (name "unconnected-(MCU1-RC5-Pad36)") (class "Default")
      (node (ref "MCU1") (pin "36") (pinfunction "RC5_36") (pintype "bidirectional"))
    )
    (net (code "119") (name "unconnected-(MCU1-RC6-Pad31)") (class "Default")
      (node (ref "MCU1") (pin "31") (pinfunction "RC6_31") (pintype "bidirectional"))
    )
    (net (code "120") (name "unconnected-(MCU1-RC7-Pad32)") (class "Default")
      (node (ref "MCU1") (pin "32") (pinfunction "RC7_32") (pintype "bidirectional"))
    )
    (net (code "121") (name "unconnected-(MCU1-RG4-Pad8)") (class "Default")
      (node (ref "MCU1") (pin "8") (pinfunction "RG4_8") (pintype "bidirectional"))
    )
    (net (code "122") (name "unconnected-(RTC1-CLKOUT{slash}~{IRQ3}-Pad8)") (class "Default")
      (node (ref "RTC1") (pin "8") (pinfunction "CLKOUT/~{IRQ3}_8") (pintype "bidirectional"))
    )
    (net (code "123") (name "unconnected-(RTC1-XI-Pad16)") (class "Default")
      (node (ref "RTC1") (pin "16") (pinfunction "XI_16") (pintype "bidirectional"))
    )
    (net (code "124") (name "unconnected-(RTC1-XO-Pad15)") (class "Default")
      (node (ref "RTC1") (pin "15") (pinfunction "XO_15") (pintype "bidirectional"))
    )
    (net (code "125") (name "unconnected-(RTC1-~{RST}-Pad1)") (class "Default")
      (node (ref "RTC1") (pin "1") (pinfunction "~{RST}_1") (pintype "bidirectional"))
    )
    (net (code "126") (name "unconnected-(RTC1-~{TIRQ}-Pad12)") (class "Default")
      (node (ref "RTC1") (pin "12") (pinfunction "~{TIRQ}_12") (pintype "bidirectional"))
    )
    (net (code "127") (name "unconnected-(U16B-SA-Pad9)") (class "Default")
      (node (ref "U16") (pin "9") (pinfunction "SA_9") (pintype "bidirectional"))
    )
    (net (code "128") (name "unconnected-(U17A-SB-Pad3)") (class "Default")
      (node (ref "U17") (pin "3") (pinfunction "SB_3") (pintype "bidirectional"))
    )
    (net (code "129") (name "unconnected-(U17B-SB-Pad7)") (class "Default")
      (node (ref "U17") (pin "7") (pinfunction "SB_7") (pintype "bidirectional"))
    )
  )
)
